# STM32F.net
KiCad netlist of a schematic drawn in Altium Designer
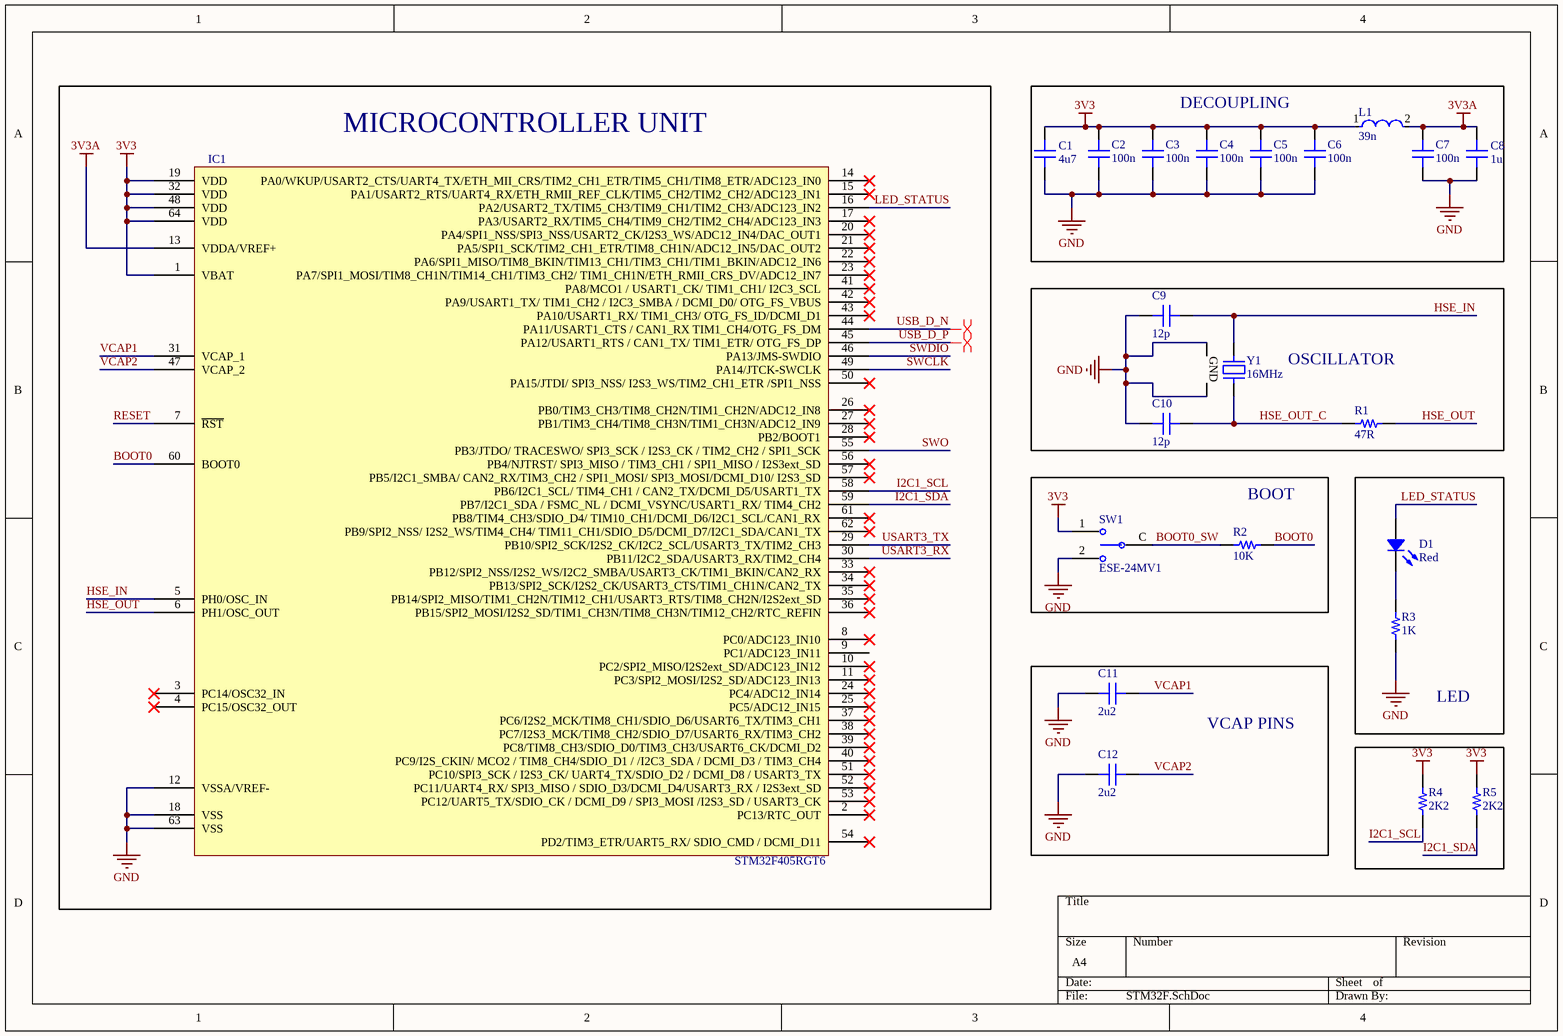
[diagram p0: STM32F.SchDoc]

(export (version "E")
  (design (tool "Eeschema 10.0.6"))
  (components
    (comp (ref "C1")
      (value "4u7")
      (footprint "CAP 0805_2012")
      (description "CAP CER 2200PF 16V X7R 0805")
      (fields (field (name "PART NUMBER") "C0805C222K4RAC7800") (field (name "MANUFACTURER") "KEMET"))
      (libsource (lib "Celestial Altium Library - altium_library") (part "Capacitor"))
    )
    (comp (ref "C2")
      (value "100n")
      (footprint "CAP 0603_1608")
      (description "CAP CER SMD 0603 .1UF 5% X7R 16V")
      (fields (field (name "PART NUMBER") "C0603C104J4RAC7013") (field (name "MANUFACTURER") "KEMET"))
      (libsource (lib "Celestial Altium Library - altium_library") (part "Capacitor"))
    )
    (comp (ref "C3")
      (value "100n")
      (footprint "CAP 0603_1608")
      (description "CAP CER SMD 0603 .1UF 5% X7R 16V")
      (fields (field (name "PART NUMBER") "C0603C104J4RAC7013") (field (name "MANUFACTURER") "KEMET"))
      (libsource (lib "Celestial Altium Library - altium_library") (part "Capacitor"))
    )
    (comp (ref "C4")
      (value "100n")
      (footprint "CAP 0603_1608")
      (description "CAP CER SMD 0603 .1UF 5% X7R 16V")
      (fields (field (name "PART NUMBER") "C0603C104J4RAC7013") (field (name "MANUFACTURER") "KEMET"))
      (libsource (lib "Celestial Altium Library - altium_library") (part "Capacitor"))
    )
    (comp (ref "C5")
      (value "100n")
      (footprint "CAP 0603_1608")
      (description "CAP CER SMD 0603 .1UF 5% X7R 16V")
      (fields (field (name "PART NUMBER") "C0603C104J4RAC7013") (field (name "MANUFACTURER") "KEMET"))
      (libsource (lib "Celestial Altium Library - altium_library") (part "Capacitor"))
    )
    (comp (ref "C6")
      (value "100n")
      (footprint "CAP 0603_1608")
      (description "CAP CER SMD 0603 .1UF 5% X7R 16V")
      (fields (field (name "PART NUMBER") "C0603C104J4RAC7013") (field (name "MANUFACTURER") "KEMET"))
      (libsource (lib "Celestial Altium Library - altium_library") (part "Capacitor"))
    )
    (comp (ref "C7")
      (value "100n")
      (footprint "CAP 0603_1608")
      (description "CAP CER SMD 0603 .1UF 5% X7R 16V")
      (fields (field (name "PART NUMBER") "C0603C104J4RAC7013") (field (name "MANUFACTURER") "KEMET"))
      (libsource (lib "Celestial Altium Library - altium_library") (part "Capacitor"))
    )
    (comp (ref "C8")
      (value "1u")
      (footprint "CAP 0805_2012")
      (description "CAP CER 2200PF 16V X7R 0805")
      (fields (field (name "PART NUMBER") "C0805C222K4RAC7800") (field (name "MANUFACTURER") "KEMET"))
      (libsource (lib "Celestial Altium Library - altium_library") (part "Capacitor"))
    )
    (comp (ref "C9")
      (value "12p")
      (footprint "CAP 0603_1608")
      (description "CAP CER SMD 0603 .1UF 5% X7R 16V")
      (fields (field (name "PART NUMBER") "C0603C104J4RAC7013") (field (name "MANUFACTURER") "KEMET"))
      (libsource (lib "Celestial Altium Library - altium_library") (part "Capacitor"))
    )
    (comp (ref "C10")
      (value "12p")
      (footprint "CAP 0603_1608")
      (description "CAP CER SMD 0603 .1UF 5% X7R 16V")
      (fields (field (name "PART NUMBER") "C0603C104J4RAC7013") (field (name "MANUFACTURER") "KEMET"))
      (libsource (lib "Celestial Altium Library - altium_library") (part "Capacitor"))
    )
    (comp (ref "C11")
      (value "2u2")
      (footprint "CAP 0603_1608")
      (description "CAP CER SMD 0603 .1UF 5% X7R 16V")
      (fields (field (name "PART NUMBER") "C0603C104J4RAC7013") (field (name "MANUFACTURER") "KEMET"))
      (libsource (lib "Celestial Altium Library - altium_library") (part "Capacitor"))
    )
    (comp (ref "C12")
      (value "2u2")
      (footprint "CAP 0603_1608")
      (description "CAP CER SMD 0603 .1UF 5% X7R 16V")
      (fields (field (name "PART NUMBER") "C0603C104J4RAC7013") (field (name "MANUFACTURER") "KEMET"))
      (libsource (lib "Celestial Altium Library - altium_library") (part "Capacitor"))
    )
    (comp (ref "D1")
      (value "Red")
      (footprint "LED 0603_1608 RED")
      (description "LED RED 0603")
      (fields (field (name "PART NUMBER") "APT1608SEC/J3-AMT") (field (name "MANUFACTURER") "Kingbright"))
      (libsource (lib "Celestial Altium Library - altium_library") (part "LED"))
    )
    (comp (ref "IC1")
      (value "STM32F405RGT6")
      (footprint "ST LQFP-64 10X10MM")
      (description "IC MCU 32BIT 1MB FLASH 64LQFP")
      (fields (field (name "MANUFACTURER") "STMicroelectronics"))
      (libsource (lib "Celestial Altium Library - altium_library") (part "ST STM32F405RGT6 64PIN"))
    )
    (comp (ref "L1")
      (value "39n")
      (footprint "FP-LQW18AN_00-MFG")
      (description "Wire Wound RF Inductor 39nH ±2% 400mA 0.26Ω 0603 (1608)")
      (fields (field (name "TOLERANCE") "2%"))
      (libsource (lib "Altium Content Vault") (part "725321dda6339637d4d059423bc1c3c"))
    )
    (comp (ref "R1")
      (value "47R")
      (footprint "RES 0603_1608")
      (description "RES SMD 47 OHM 1% 1/10W 0603")
      (fields (field (name "PART NUMBER") "AC0603FR-0747RL") (field (name "MANUFACTURER") "Yageo"))
      (libsource (lib "Celestial Altium Library - altium_library") (part "Resistor"))
    )
    (comp (ref "R2")
      (value "10K")
      (footprint "RES 0603_1608")
      (description "RES SMD 47 OHM 1% 1/10W 0603")
      (fields (field (name "PART NUMBER") "AC0603FR-0747RL") (field (name "MANUFACTURER") "Yageo"))
      (libsource (lib "Celestial Altium Library - altium_library") (part "Resistor"))
    )
    (comp (ref "R3")
      (value "1K")
      (footprint "RES 0603_1608")
      (description "RES SMD 47 OHM 1% 1/10W 0603")
      (fields (field (name "PART NUMBER") "AC0603FR-0747RL") (field (name "MANUFACTURER") "Yageo"))
      (libsource (lib "Celestial Altium Library - altium_library") (part "Resistor"))
    )
    (comp (ref "R4")
      (value "2K2")
      (footprint "RES 0603_1608")
      (description "RES SMD 47 OHM 1% 1/10W 0603")
      (fields (field (name "PART NUMBER") "AC0603FR-0747RL") (field (name "MANUFACTURER") "Yageo"))
      (libsource (lib "Celestial Altium Library - altium_library") (part "Resistor"))
    )
    (comp (ref "R5")
      (value "2K2")
      (footprint "RES 0603_1608")
      (description "RES SMD 47 OHM 1% 1/10W 0603")
      (fields (field (name "PART NUMBER") "AC0603FR-0747RL") (field (name "MANUFACTURER") "Yageo"))
      (libsource (lib "Celestial Altium Library - altium_library") (part "Resistor"))
    )
    (comp (ref "SW1")
      (value "ESE-24MV1")
      (footprint "FP-ESE-24MV1-MFG")
      (description "SWITCH DETECTOR SPDT 10MA 5V")
      (libsource (lib "Altium Content Vault") (part "c366afd49124e13d88e35c0c226052d"))
    )
    (comp (ref "Y1")
      (value "16MHz")
      (footprint "ABRACON ABM10")
      (description "CRYSTAL 16.0000MHZ 10PF SMD")
      (fields
        (field (name "PART NUMBER") "ABM10-16.000MHZ-E20-T")
        (field (name "MANUFACTURER") "Abracon LLC")
      )
      (libsource (lib "Celestial Altium Library - altium_library") (part "Abracon Crystal ABM10"))
    )
  )
  (nets
    (net (code "1") (name "/BOOT0") (class "Default")
      (node (ref "IC1") (pin "60") (pinfunction "BOOT0_60") (pintype "passive"))
      (node (ref "R2") (pin "2") (pinfunction "2_2") (pintype "passive"))
    )
    (net (code "2") (name "/BOOT0_SW") (class "Default")
      (node (ref "R2") (pin "1") (pinfunction "1_1") (pintype "passive"))
      (node (ref "SW1") (pin "C") (pinfunction "C_C") (pintype "passive"))
    )
    (net (code "3") (name "/HSE_IN") (class "Default")
      (node (ref "C9") (pin "1") (pinfunction "1_1") (pintype "passive"))
      (node (ref "IC1") (pin "5") (pinfunction "PH0/OSC_IN_5") (pintype "passive"))
      (node (ref "Y1") (pin "1") (pinfunction "1_1") (pintype "passive"))
    )
    (net (code "4") (name "/HSE_OUT") (class "Default")
      (node (ref "IC1") (pin "6") (pinfunction "PH1/OSC_OUT_6") (pintype "passive"))
      (node (ref "R1") (pin "2") (pinfunction "2_2") (pintype "passive"))
    )
    (net (code "5") (name "/HSE_OUT_C") (class "Default")
      (node (ref "C10") (pin "1") (pinfunction "1_1") (pintype "passive"))
      (node (ref "R1") (pin "1") (pinfunction "1_1") (pintype "passive"))
      (node (ref "Y1") (pin "3") (pinfunction "3_3") (pintype "passive"))
    )
    (net (code "6") (name "/I2C1_SCL") (class "Default")
      (node (ref "IC1") (pin "58") (pinfunction "PB6/I2C1_SCL/_TIM4_CH1_/_CAN2_TX/DCMI_D5/USART1_TX_58") (pintype "passive"))
      (node (ref "R4") (pin "1") (pinfunction "1_1") (pintype "passive"))
    )
    (net (code "7") (name "/I2C1_SDA") (class "Default")
      (node (ref "IC1") (pin "59") (pinfunction "PB7/I2C1_SDA_/_FSMC_NL_/_DCMI_VSYNC/USART1_RX/_TIM4_CH2_59") (pintype "passive"))
      (node (ref "R5") (pin "1") (pinfunction "1_1") (pintype "passive"))
    )
    (net (code "8") (name "/LED_STATUS") (class "Default")
      (node (ref "D1") (pin "1") (pinfunction "1_1") (pintype "passive"))
      (node (ref "IC1") (pin "16") (pinfunction "PA2/USART2_TX/TIM5_CH3/TIM9_CH1/TIM2_CH3/ADC123_IN2_16") (pintype "passive"))
    )
    (net (code "9") (name "/RESET") (class "Default")
      (node (ref "IC1") (pin "7") (pinfunction "~{RST}_7") (pintype "passive"))
    )
    (net (code "10") (name "/SWCLK") (class "Default")
      (node (ref "IC1") (pin "49") (pinfunction "PA14/JTCK-SWCLK_49") (pintype "passive"))
    )
    (net (code "11") (name "/SWDIO") (class "Default")
      (node (ref "IC1") (pin "46") (pinfunction "PA13/JMS-SWDIO_46") (pintype "passive"))
    )
    (net (code "12") (name "/SWO") (class "Default")
      (node (ref "IC1") (pin "55") (pinfunction "PB3/JTDO/_TRACESWO/_SPI3_SCK_/_I2S3_CK_/_TIM2_CH2_/_SPI1_SCK_55") (pintype "passive"))
    )
    (net (code "13") (name "/USART3_RX") (class "Default")
      (node (ref "IC1") (pin "30") (pinfunction "PB11/I2C2_SDA/USART3_RX/TIM2_CH4_30") (pintype "passive"))
    )
    (net (code "14") (name "/USART3_TX") (class "Default")
      (node (ref "IC1") (pin "29") (pinfunction "PB10/SPI2_SCK/I2S2_CK/I2C2_SCL/USART3_TX/TIM2_CH3_29") (pintype "passive"))
    )
    (net (code "15") (name "/USB_D_N") (class "Default")
      (node (ref "IC1") (pin "44") (pinfunction "PA11/USART1_CTS_/_CAN1_RX_TIM1_CH4/OTG_FS_DM_44") (pintype "passive"))
    )
    (net (code "16") (name "/USB_D_P") (class "Default")
      (node (ref "IC1") (pin "45") (pinfunction "PA12/USART1_RTS_/_CAN1_TX/_TIM1_ETR/_OTG_FS_DP_45") (pintype "passive"))
    )
    (net (code "17") (name "/VCAP1") (class "Default")
      (node (ref "C11") (pin "1") (pinfunction "1_1") (pintype "passive"))
      (node (ref "IC1") (pin "31") (pinfunction "VCAP_1_31") (pintype "passive"))
    )
    (net (code "18") (name "/VCAP2") (class "Default")
      (node (ref "C12") (pin "1") (pinfunction "1_1") (pintype "passive"))
      (node (ref "IC1") (pin "47") (pinfunction "VCAP_2_47") (pintype "passive"))
    )
    (net (code "19") (name "3V3") (class "Default")
      (node (ref "C1") (pin "2") (pinfunction "2_2") (pintype "passive"))
      (node (ref "C2") (pin "2") (pinfunction "2_2") (pintype "passive"))
      (node (ref "C3") (pin "2") (pinfunction "2_2") (pintype "passive"))
      (node (ref "C4") (pin "2") (pinfunction "2_2") (pintype "passive"))
      (node (ref "C5") (pin "2") (pinfunction "2_2") (pintype "passive"))
      (node (ref "C6") (pin "2") (pinfunction "2_2") (pintype "passive"))
      (node (ref "IC1") (pin "1") (pinfunction "VBAT_1") (pintype "passive"))
      (node (ref "IC1") (pin "19") (pinfunction "VDD_19") (pintype "passive"))
      (node (ref "IC1") (pin "32") (pinfunction "VDD_32") (pintype "passive"))
      (node (ref "IC1") (pin "48") (pinfunction "VDD_48") (pintype "passive"))
      (node (ref "IC1") (pin "64") (pinfunction "VDD_64") (pintype "passive"))
      (node (ref "L1") (pin "1") (pinfunction "1_1") (pintype "passive"))
      (node (ref "R4") (pin "2") (pinfunction "2_2") (pintype "passive"))
      (node (ref "R5") (pin "2") (pinfunction "2_2") (pintype "passive"))
      (node (ref "SW1") (pin "1") (pinfunction "1_1") (pintype "passive"))
    )
    (net (code "20") (name "3V3A") (class "Default")
      (node (ref "C7") (pin "2") (pinfunction "2_2") (pintype "passive"))
      (node (ref "C8") (pin "2") (pinfunction "2_2") (pintype "passive"))
      (node (ref "IC1") (pin "13") (pinfunction "VDDA/VREF+_13") (pintype "passive"))
      (node (ref "L1") (pin "2") (pinfunction "2_2") (pintype "passive"))
    )
    (net (code "21") (name "GND") (class "Default")
      (node (ref "C1") (pin "1") (pinfunction "1_1") (pintype "passive"))
      (node (ref "C10") (pin "2") (pinfunction "2_2") (pintype "passive"))
      (node (ref "C11") (pin "2") (pinfunction "2_2") (pintype "passive"))
      (node (ref "C12") (pin "2") (pinfunction "2_2") (pintype "passive"))
      (node (ref "C2") (pin "1") (pinfunction "1_1") (pintype "passive"))
      (node (ref "C3") (pin "1") (pinfunction "1_1") (pintype "passive"))
      (node (ref "C4") (pin "1") (pinfunction "1_1") (pintype "passive"))
      (node (ref "C5") (pin "1") (pinfunction "1_1") (pintype "passive"))
      (node (ref "C6") (pin "1") (pinfunction "1_1") (pintype "passive"))
      (node (ref "C7") (pin "1") (pinfunction "1_1") (pintype "passive"))
      (node (ref "C8") (pin "1") (pinfunction "1_1") (pintype "passive"))
      (node (ref "C9") (pin "2") (pinfunction "2_2") (pintype "passive"))
      (node (ref "IC1") (pin "12") (pinfunction "VSSA/VREF-_12") (pintype "passive"))
      (node (ref "IC1") (pin "18") (pinfunction "VSS_18") (pintype "passive"))
      (node (ref "IC1") (pin "63") (pinfunction "VSS_63") (pintype "passive"))
      (node (ref "R3") (pin "1") (pinfunction "1_1") (pintype "passive"))
      (node (ref "SW1") (pin "2") (pinfunction "2_2") (pintype "passive"))
      (node (ref "Y1") (pin "2") (pinfunction "GND_2") (pintype "passive"))
      (node (ref "Y1") (pin "4") (pinfunction "GND_4") (pintype "passive"))
    )
    (net (code "22") (name "Net-(D1-Pad2)") (class "Default")
      (node (ref "D1") (pin "2") (pinfunction "2_2") (pintype "passive"))
      (node (ref "R3") (pin "2") (pinfunction "2_2") (pintype "passive"))
    )
    (net (code "23") (name "unconnected-(IC1-PA0{slash}WKUP{slash}USART2_CTS{slash}UART4_TX{slash}ETH_MII_CRS{slash}TIM2_CH1_ETR{slash}TIM5_CH1{slash}TIM8_ETR{slash}ADC123_IN0-Pad14)") (class "Default")
      (node (ref "IC1") (pin "14") (pinfunction "PA0/WKUP/USART2_CTS/UART4_TX/ETH_MII_CRS/TIM2_CH1_ETR/TIM5_CH1/TIM8_ETR/ADC123_IN0_14") (pintype "passive+no_connect"))
    )
    (net (code "24") (name "unconnected-(IC1-PA1{slash}USART2_RTS{slash}UART4_RX{slash}ETH_RMII_REF_CLK{slash}TIM5_CH2{slash}TIM2_CH2{slash}ADC123_IN1-Pad15)") (class "Default")
      (node (ref "IC1") (pin "15") (pinfunction "PA1/USART2_RTS/UART4_RX/ETH_RMII_REF_CLK/TIM5_CH2/TIM2_CH2/ADC123_IN1_15") (pintype "passive+no_connect"))
    )
    (net (code "25") (name "unconnected-(IC1-PA3{slash}USART2_RX{slash}TIM5_CH4{slash}TIM9_CH2{slash}TIM2_CH4{slash}ADC123_IN3-Pad17)") (class "Default")
      (node (ref "IC1") (pin "17") (pinfunction "PA3/USART2_RX/TIM5_CH4/TIM9_CH2/TIM2_CH4/ADC123_IN3_17") (pintype "passive+no_connect"))
    )
    (net (code "26") (name "unconnected-(IC1-PA4{slash}SPI1_NSS{slash}SPI3_NSS{slash}USART2_CK{slash}I2S3_WS{slash}ADC12_IN4{slash}DAC_OUT1-Pad20)") (class "Default")
      (node (ref "IC1") (pin "20") (pinfunction "PA4/SPI1_NSS/SPI3_NSS/USART2_CK/I2S3_WS/ADC12_IN4/DAC_OUT1_20") (pintype "passive+no_connect"))
    )
    (net (code "27") (name "unconnected-(IC1-PA5{slash}SPI1_SCK{slash}TIM2_CH1_ETR{slash}TIM8_CH1N{slash}ADC12_IN5{slash}DAC_OUT2-Pad21)") (class "Default")
      (node (ref "IC1") (pin "21") (pinfunction "PA5/SPI1_SCK/TIM2_CH1_ETR/TIM8_CH1N/ADC12_IN5/DAC_OUT2_21") (pintype "passive+no_connect"))
    )
    (net (code "28") (name "unconnected-(IC1-PA6{slash}SPI1_MISO{slash}TIM8_BKIN{slash}TIM13_CH1{slash}TIM3_CH1{slash}TIM1_BKIN{slash}ADC12_IN6-Pad22)") (class "Default")
      (node (ref "IC1") (pin "22") (pinfunction "PA6/SPI1_MISO/TIM8_BKIN/TIM13_CH1/TIM3_CH1/TIM1_BKIN/ADC12_IN6_22") (pintype "passive+no_connect"))
    )
    (net (code "29") (name "unconnected-(IC1-PA7{slash}SPI1_MOSI{slash}TIM8_CH1N{slash}TIM14_CH1{slash}TIM3_CH2{slash}_TIM1_CH1N{slash}ETH_RMII_CRS_DV{slash}ADC12_IN7-Pad23)") (class "Default")
      (node (ref "IC1") (pin "23") (pinfunction "PA7/SPI1_MOSI/TIM8_CH1N/TIM14_CH1/TIM3_CH2/_TIM1_CH1N/ETH_RMII_CRS_DV/ADC12_IN7_23") (pintype "passive+no_connect"))
    )
    (net (code "30") (name "unconnected-(IC1-PA8{slash}MCO1_{slash}_USART1_CK{slash}_TIM1_CH1{slash}_I2C3_SCL-Pad41)") (class "Default")
      (node (ref "IC1") (pin "41") (pinfunction "PA8/MCO1_/_USART1_CK/_TIM1_CH1/_I2C3_SCL_41") (pintype "passive+no_connect"))
    )
    (net (code "31") (name "unconnected-(IC1-PA9{slash}USART1_TX{slash}_TIM1_CH2_{slash}_I2C3_SMBA_{slash}_DCMI_D0{slash}_OTG_FS_VBUS-Pad42)") (class "Default")
      (node (ref "IC1") (pin "42") (pinfunction "PA9/USART1_TX/_TIM1_CH2_/_I2C3_SMBA_/_DCMI_D0/_OTG_FS_VBUS_42") (pintype "passive+no_connect"))
    )
    (net (code "32") (name "unconnected-(IC1-PA10{slash}USART1_RX{slash}_TIM1_CH3{slash}_OTG_FS_ID{slash}DCMI_D1-Pad43)") (class "Default")
      (node (ref "IC1") (pin "43") (pinfunction "PA10/USART1_RX/_TIM1_CH3/_OTG_FS_ID/DCMI_D1_43") (pintype "passive+no_connect"))
    )
    (net (code "33") (name "unconnected-(IC1-PA15{slash}JTDI{slash}_SPI3_NSS{slash}_I2S3_WS{slash}TIM2_CH1_ETR_{slash}SPI1_NSS-Pad50)") (class "Default")
      (node (ref "IC1") (pin "50") (pinfunction "PA15/JTDI/_SPI3_NSS/_I2S3_WS/TIM2_CH1_ETR_/SPI1_NSS_50") (pintype "passive+no_connect"))
    )
    (net (code "34") (name "unconnected-(IC1-PB0{slash}TIM3_CH3{slash}TIM8_CH2N{slash}TIM1_CH2N{slash}ADC12_IN8-Pad26)") (class "Default")
      (node (ref "IC1") (pin "26") (pinfunction "PB0/TIM3_CH3/TIM8_CH2N/TIM1_CH2N/ADC12_IN8_26") (pintype "passive+no_connect"))
    )
    (net (code "35") (name "unconnected-(IC1-PB1{slash}TIM3_CH4{slash}TIM8_CH3N{slash}TIM1_CH3N{slash}ADC12_IN9-Pad27)") (class "Default")
      (node (ref "IC1") (pin "27") (pinfunction "PB1/TIM3_CH4/TIM8_CH3N/TIM1_CH3N/ADC12_IN9_27") (pintype "passive+no_connect"))
    )
    (net (code "36") (name "unconnected-(IC1-PB2{slash}BOOT1-Pad28)") (class "Default")
      (node (ref "IC1") (pin "28") (pinfunction "PB2/BOOT1_28") (pintype "passive+no_connect"))
    )
    (net (code "37") (name "unconnected-(IC1-PB4{slash}NJTRST{slash}_SPI3_MISO_{slash}_TIM3_CH1_{slash}_SPI1_MISO_{slash}_I2S3ext_SD-Pad56)") (class "Default")
      (node (ref "IC1") (pin "56") (pinfunction "PB4/NJTRST/_SPI3_MISO_/_TIM3_CH1_/_SPI1_MISO_/_I2S3ext_SD_56") (pintype "passive+no_connect"))
    )
    (net (code "38") (name "unconnected-(IC1-PB5{slash}I2C1_SMBA{slash}_CAN2_RX{slash}TIM3_CH2_{slash}_SPI1_MOSI{slash}_SPI3_MOSI{slash}DCMI_D10{slash}_I2S3_SD-Pad57)") (class "Default")
      (node (ref "IC1") (pin "57") (pinfunction "PB5/I2C1_SMBA/_CAN2_RX/TIM3_CH2_/_SPI1_MOSI/_SPI3_MOSI/DCMI_D10/_I2S3_SD_57") (pintype "passive+no_connect"))
    )
    (net (code "39") (name "unconnected-(IC1-PB8{slash}TIM4_CH3{slash}SDIO_D4{slash}_TIM10_CH1{slash}DCMI_D6{slash}I2C1_SCL{slash}CAN1_RX-Pad61)") (class "Default")
      (node (ref "IC1") (pin "61") (pinfunction "PB8/TIM4_CH3/SDIO_D4/_TIM10_CH1/DCMI_D6/I2C1_SCL/CAN1_RX_61") (pintype "passive+no_connect"))
    )
    (net (code "40") (name "unconnected-(IC1-PB9{slash}SPI2_NSS{slash}_I2S2_WS{slash}TIM4_CH4{slash}_TIM11_CH1{slash}SDIO_D5{slash}DCMI_D7{slash}I2C1_SDA{slash}CAN1_TX-Pad62)") (class "Default")
      (node (ref "IC1") (pin "62") (pinfunction "PB9/SPI2_NSS/_I2S2_WS/TIM4_CH4/_TIM11_CH1/SDIO_D5/DCMI_D7/I2C1_SDA/CAN1_TX_62") (pintype "passive+no_connect"))
    )
    (net (code "41") (name "unconnected-(IC1-PB12{slash}SPI2_NSS{slash}I2S2_WS{slash}I2C2_SMBA{slash}USART3_CK{slash}TIM1_BKIN{slash}CAN2_RX-Pad33)") (class "Default")
      (node (ref "IC1") (pin "33") (pinfunction "PB12/SPI2_NSS/I2S2_WS/I2C2_SMBA/USART3_CK/TIM1_BKIN/CAN2_RX_33") (pintype "passive+no_connect"))
    )
    (net (code "42") (name "unconnected-(IC1-PB13{slash}SPI2_SCK{slash}I2S2_CK{slash}USART3_CTS{slash}TIM1_CH1N{slash}CAN2_TX-Pad34)") (class "Default")
      (node (ref "IC1") (pin "34") (pinfunction "PB13/SPI2_SCK/I2S2_CK/USART3_CTS/TIM1_CH1N/CAN2_TX_34") (pintype "passive+no_connect"))
    )
    (net (code "43") (name "unconnected-(IC1-PB14{slash}SPI2_MISO{slash}TIM1_CH2N{slash}TIM12_CH1{slash}USART3_RTS{slash}TIM8_CH2N{slash}I2S2ext_SD-Pad35)") (class "Default")
      (node (ref "IC1") (pin "35") (pinfunction "PB14/SPI2_MISO/TIM1_CH2N/TIM12_CH1/USART3_RTS/TIM8_CH2N/I2S2ext_SD_35") (pintype "passive+no_connect"))
    )
    (net (code "44") (name "unconnected-(IC1-PB15{slash}SPI2_MOSI{slash}I2S2_SD{slash}TIM1_CH3N{slash}TIM8_CH3N{slash}TIM12_CH2{slash}RTC_REFIN-Pad36)") (class "Default")
      (node (ref "IC1") (pin "36") (pinfunction "PB15/SPI2_MOSI/I2S2_SD/TIM1_CH3N/TIM8_CH3N/TIM12_CH2/RTC_REFIN_36") (pintype "passive+no_connect"))
    )
    (net (code "45") (name "unconnected-(IC1-PC0{slash}ADC123_IN10-Pad8)") (class "Default")
      (node (ref "IC1") (pin "8") (pinfunction "PC0/ADC123_IN10_8") (pintype "passive+no_connect"))
    )
    (net (code "46") (name "unconnected-(IC1-PC1{slash}ADC123_IN11-Pad9)") (class "Default")
      (node (ref "IC1") (pin "9") (pinfunction "PC1/ADC123_IN11_9") (pintype "passive"))
    )
    (net (code "47") (name "unconnected-(IC1-PC2{slash}SPI2_MISO{slash}I2S2ext_SD{slash}ADC123_IN12-Pad10)") (class "Default")
      (node (ref "IC1") (pin "10") (pinfunction "PC2/SPI2_MISO/I2S2ext_SD/ADC123_IN12_10") (pintype "passive+no_connect"))
    )
    (net (code "48") (name "unconnected-(IC1-PC3{slash}SPI2_MOSI{slash}I2S2_SD{slash}ADC123_IN13-Pad11)") (class "Default")
      (node (ref "IC1") (pin "11") (pinfunction "PC3/SPI2_MOSI/I2S2_SD/ADC123_IN13_11") (pintype "passive+no_connect"))
    )
    (net (code "49") (name "unconnected-(IC1-PC4{slash}ADC12_IN14-Pad24)") (class "Default")
      (node (ref "IC1") (pin "24") (pinfunction "PC4/ADC12_IN14_24") (pintype "passive+no_connect"))
    )
    (net (code "50") (name "unconnected-(IC1-PC5{slash}ADC12_IN15-Pad25)") (class "Default")
      (node (ref "IC1") (pin "25") (pinfunction "PC5/ADC12_IN15_25") (pintype "passive+no_connect"))
    )
    (net (code "51") (name "unconnected-(IC1-PC6{slash}I2S2_MCK{slash}TIM8_CH1{slash}SDIO_D6{slash}USART6_TX{slash}TIM3_CH1-Pad37)") (class "Default")
      (node (ref "IC1") (pin "37") (pinfunction "PC6/I2S2_MCK/TIM8_CH1/SDIO_D6/USART6_TX/TIM3_CH1_37") (pintype "passive+no_connect"))
    )
    (net (code "52") (name "unconnected-(IC1-PC7{slash}I2S3_MCK{slash}TIM8_CH2{slash}SDIO_D7{slash}USART6_RX{slash}TIM3_CH2-Pad38)") (class "Default")
      (node (ref "IC1") (pin "38") (pinfunction "PC7/I2S3_MCK/TIM8_CH2/SDIO_D7/USART6_RX/TIM3_CH2_38") (pintype "passive+no_connect"))
    )
    (net (code "53") (name "unconnected-(IC1-PC8{slash}TIM8_CH3{slash}SDIO_D0{slash}TIM3_CH3{slash}USART6_CK{slash}DCMI_D2-Pad39)") (class "Default")
      (node (ref "IC1") (pin "39") (pinfunction "PC8/TIM8_CH3/SDIO_D0/TIM3_CH3/USART6_CK/DCMI_D2_39") (pintype "passive+no_connect"))
    )
    (net (code "54") (name "unconnected-(IC1-PC9{slash}I2S_CKIN{slash}_MCO2_{slash}_TIM8_CH4{slash}SDIO_D1_{slash}_{slash}I2C3_SDA_{slash}_DCMI_D3_{slash}_TIM3_CH4-Pad40)") (class "Default")
      (node (ref "IC1") (pin "40") (pinfunction "PC9/I2S_CKIN/_MCO2_/_TIM8_CH4/SDIO_D1_/_/I2C3_SDA_/_DCMI_D3_/_TIM3_CH4_40") (pintype "passive+no_connect"))
    )
    (net (code "55") (name "unconnected-(IC1-PC10{slash}SPI3_SCK_{slash}_I2S3_CK{slash}_UART4_TX{slash}SDIO_D2_{slash}_DCMI_D8_{slash}_USART3_TX-Pad51)") (class "Default")
      (node (ref "IC1") (pin "51") (pinfunction "PC10/SPI3_SCK_/_I2S3_CK/_UART4_TX/SDIO_D2_/_DCMI_D8_/_USART3_TX_51") (pintype "passive+no_connect"))
    )
    (net (code "56") (name "unconnected-(IC1-PC11{slash}UART4_RX{slash}_SPI3_MISO_{slash}_SDIO_D3{slash}DCMI_D4{slash}USART3_RX_{slash}_I2S3ext_SD-Pad52)") (class "Default")
      (node (ref "IC1") (pin "52") (pinfunction "PC11/UART4_RX/_SPI3_MISO_/_SDIO_D3/DCMI_D4/USART3_RX_/_I2S3ext_SD_52") (pintype "passive+no_connect"))
    )
    (net (code "57") (name "unconnected-(IC1-PC12{slash}UART5_TX{slash}SDIO_CK_{slash}_DCMI_D9_{slash}_SPI3_MOSI_{slash}I2S3_SD_{slash}_USART3_CK-Pad53)") (class "Default")
      (node (ref "IC1") (pin "53") (pinfunction "PC12/UART5_TX/SDIO_CK_/_DCMI_D9_/_SPI3_MOSI_/I2S3_SD_/_USART3_CK_53") (pintype "passive+no_connect"))
    )
    (net (code "58") (name "unconnected-(IC1-PC13{slash}RTC_OUT-Pad2)") (class "Default")
      (node (ref "IC1") (pin "2") (pinfunction "PC13/RTC_OUT_2") (pintype "passive+no_connect"))
    )
    (net (code "59") (name "unconnected-(IC1-PC14{slash}OSC32_IN-Pad3)") (class "Default")
      (node (ref "IC1") (pin "3") (pinfunction "PC14/OSC32_IN_3") (pintype "passive+no_connect"))
    )
    (net (code "60") (name "unconnected-(IC1-PC15{slash}OSC32_OUT-Pad4)") (class "Default")
      (node (ref "IC1") (pin "4") (pinfunction "PC15/OSC32_OUT_4") (pintype "passive+no_connect"))
    )
    (net (code "61") (name "unconnected-(IC1-PD2{slash}TIM3_ETR{slash}UART5_RX{slash}_SDIO_CMD_{slash}_DCMI_D11-Pad54)") (class "Default")
      (node (ref "IC1") (pin "54") (pinfunction "PD2/TIM3_ETR/UART5_RX/_SDIO_CMD_/_DCMI_D11_54") (pintype "passive+no_connect"))
    )
  )
)
